# ESP32_ublox_IMU.net
KiCad netlist of a schematic drawn in Altium Designer
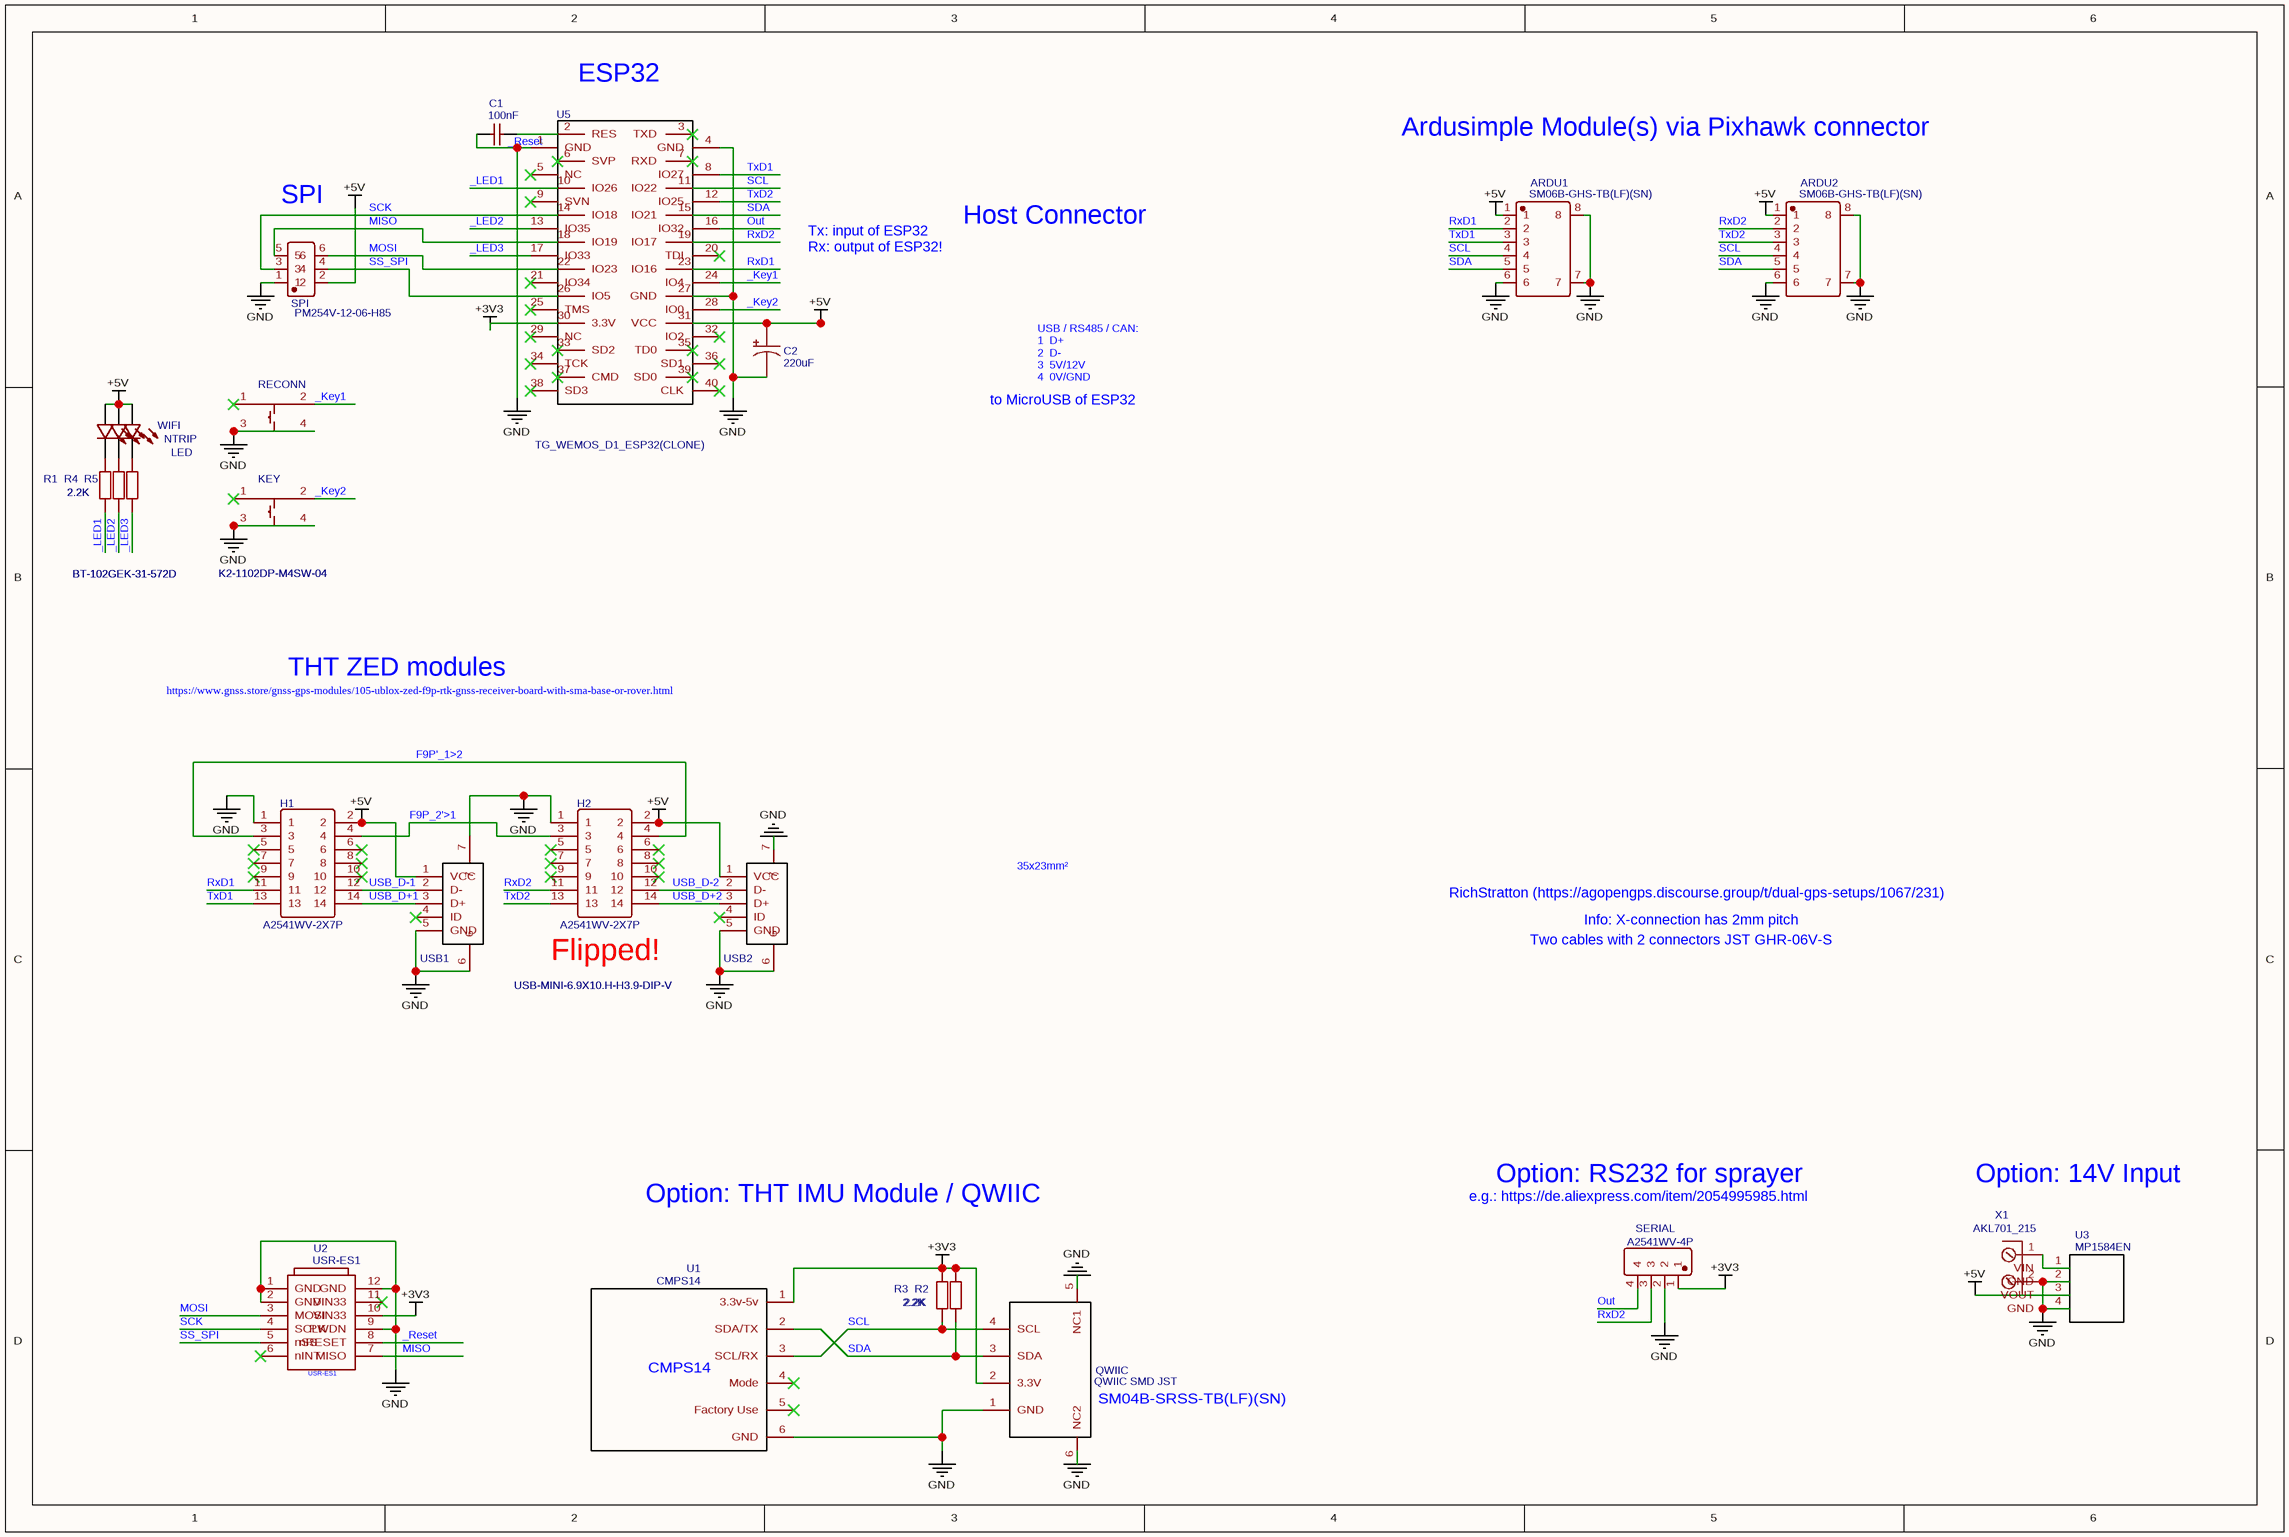
[diagram p0: ESP32 ublox IMU.schdoc]

(export (version "E")
  (design (tool "Eeschema 10.0.6"))
  (components
    (comp (ref "ARDU1")
      (value "SM06B-GHS-TB(LF)(SN)")
      (fields (field (name "BOM_SUPPLIER PART") "C133065") (field (name "CONTRIBUTOR") "LCSC"))
      (libsource (lib "altium-import") (part "root_0_SM06B-GHS-TB(LF)(SN)_"))
    )
    (comp (ref "ARDU2")
      (value "SM06B-GHS-TB(LF)(SN)")
      (fields (field (name "BOM_SUPPLIER PART") "C133065") (field (name "CONTRIBUTOR") "LCSC"))
      (libsource (lib "altium-import") (part "root_0_SM06B-GHS-TB(LF)(SN)_"))
    )
    (comp (ref "C1")
      (value "100nF")
      (fields
        (field (name "BOM_SUPPLIER PART") "C236029")
        (field (name "BOM_MANUFACTURER PART") "C320C104K5R5TA7303")
        (field (name "CONTRIBUTOR") "LCSC")
      )
      (libsource (lib "altium-import") (part "root_0_100nF_"))
    )
    (comp (ref "C2")
      (value "220uF")
      (fields
        (field (name "BOM_SUPPLIER PART") "C225866")
        (field (name "BOM_MANUFACTURER PART") "UPW1A221MED1TD")
        (field (name "CONTRIBUTOR") "LCSC")
      )
      (libsource (lib "altium-import") (part "root_0_220uF_"))
    )
    (comp (ref "H1")
      (value "A2541WV-2X7P")
      (fields
        (field (name "BOM_SUPPLIER PART") "C225522")
        (field (name "BOM_MANUFACTURER PART") "A2541WV-2x7P")
        (field (name "CONTRIBUTOR") "LCSC")
      )
      (libsource (lib "altium-import") (part "root_0_A2541WV-2X7P_"))
    )
    (comp (ref "H2")
      (value "A2541WV-2X7P")
      (fields
        (field (name "BOM_SUPPLIER PART") "C225522")
        (field (name "BOM_MANUFACTURER PART") "A2541WV-2x7P")
        (field (name "CONTRIBUTOR") "LCSC")
      )
      (libsource (lib "altium-import") (part "root_0_A2541WV-2X7P_"))
    )
    (comp (ref "KEY")
      (value "K2-1102DP-M4SW-04")
      (fields (field (name "BOM_SUPPLIER PART") "C136678") (field (name "CONTRIBUTOR") "LCSC"))
      (libsource (lib "altium-import") (part "root_0_K2-1102DP-M4SW-04_"))
    )
    (comp (ref "LED")
      (value "BT-102GEK-31-572D")
      (fields (field (name "BOM_SUPPLIER PART") "C93096"))
      (libsource (lib "altium-import") (part "root_3_BT-102GEK-31-572D_"))
    )
    (comp (ref "NTRIP")
      (value "BT-102GEK-31-572D")
      (fields (field (name "BOM_SUPPLIER PART") "C93096"))
      (libsource (lib "altium-import") (part "root_3_BT-102GEK-31-572D_"))
    )
    (comp (ref "QWIIC")
      (value "QWIIC SMD JST")
      (fields
        (field (name "BOM_MANUFACTURER PART") "SM04B-SRSS-TB(LF)(SN)")
        (field (name "BOM_SUPPLIER PART") "PRT-14417")
        (field (name "CONTRIBUTOR") "donhagen")
      )
      (libsource (lib "altium-import") (part "root_1_QWIIC SMD JST_"))
    )
    (comp (ref "R1")
      (value "2.2K")
      (fields
        (field (name "BOM_SUPPLIER PART") "C274429")
        (field (name "BOM_MANUFACTURER PART") "RNU18F2201A520NH")
        (field (name "CONTRIBUTOR") "LCSC")
      )
      (libsource (lib "altium-import") (part "root_1_2.2K_"))
    )
    (comp (ref "R2")
      (value "2.2K")
      (fields
        (field (name "BOM_SUPPLIER PART") "C274429")
        (field (name "BOM_MANUFACTURER PART") "RNU18F2201A520NH")
        (field (name "CONTRIBUTOR") "LCSC")
      )
      (libsource (lib "altium-import") (part "root_1_2.2K_"))
    )
    (comp (ref "R3")
      (value "2.2K")
      (fields
        (field (name "BOM_SUPPLIER PART") "C274429")
        (field (name "BOM_MANUFACTURER PART") "RNU18F2201A520NH")
        (field (name "CONTRIBUTOR") "LCSC")
      )
      (libsource (lib "altium-import") (part "root_1_2.2K_"))
    )
    (comp (ref "R4")
      (value "2.2K")
      (fields
        (field (name "BOM_SUPPLIER PART") "C274429")
        (field (name "BOM_MANUFACTURER PART") "RNU18F2201A520NH")
        (field (name "CONTRIBUTOR") "LCSC")
      )
      (libsource (lib "altium-import") (part "root_1_2.2K_"))
    )
    (comp (ref "R5")
      (value "2.2K")
      (fields
        (field (name "BOM_SUPPLIER PART") "C274429")
        (field (name "BOM_MANUFACTURER PART") "RNU18F2201A520NH")
        (field (name "CONTRIBUTOR") "LCSC")
      )
      (libsource (lib "altium-import") (part "root_1_2.2K_"))
    )
    (comp (ref "RECONN")
      (value "K2-1102DP-M4SW-04")
      (fields (field (name "BOM_SUPPLIER PART") "C136678") (field (name "CONTRIBUTOR") "LCSC"))
      (libsource (lib "altium-import") (part "root_0_K2-1102DP-M4SW-04_"))
    )
    (comp (ref "SERIAL")
      (value "A2541WV-4P")
      (fields (field (name "BOM_SUPPLIER PART") "C225479") (field (name "CONTRIBUTOR") "LCSC"))
      (libsource (lib "altium-import") (part "root_0_A2541WV-4P_"))
    )
    (comp (ref "SPI")
      (value "PM254V-12-06-H85")
      (fields (field (name "BOM_SUPPLIER PART") "C541853") (field (name "CONTRIBUTOR") "LCSC"))
      (libsource (lib "altium-import") (part "root_0_PM254V-12-06-H85_"))
    )
    (comp (ref "U1")
      (value "CMPS14")
      (fields (field (name "CONTRIBUTOR") "FixyNeko"))
      (libsource (lib "altium-import") (part "root_0_CMPS14_"))
    )
    (comp (ref "U2")
      (value "USR-ES1")
      (fields (field (name "CONTRIBUTOR") "tomaz.dezman_0109"))
      (libsource (lib "altium-import") (part "root_0_USR-ES1_"))
    )
    (comp (ref "U3")
      (value "MP1584EN")
      (fields (field (name "CONTRIBUTOR") "babeinlovexd"))
      (libsource (lib "altium-import") (part "root_0_MP1584EN_"))
    )
    (comp (ref "U5")
      (value "TG_WEMOS_D1_ESP32(CLONE)")
      (fields
        (field (name "BOM_MANUFACTURER PART") "New SchematicLib")
        (field (name "BOM_SUPPLIER PART") "undefined")
        (field (name "CONTRIBUTOR") "John Archbold")
      )
      (libsource (lib "altium-import") (part "root_0_TG_WEMOS_D1_ESP32(CLONE)_"))
    )
    (comp (ref "USB1")
      (value "USB-MINI-6.9X10.H-H3.9-DIP-V")
      (fields (field (name "BOM_SUPPLIER PART") "C13453") (field (name "CONTRIBUTOR") "LCSC"))
      (libsource (lib "altium-import") (part "root_3_USB-MINI-6.9X10.H-H3.9-DIP-V_"))
    )
    (comp (ref "USB2")
      (value "USB-MINI-6.9X10.H-H3.9-DIP-V")
      (fields (field (name "BOM_SUPPLIER PART") "C13453") (field (name "CONTRIBUTOR") "LCSC"))
      (libsource (lib "altium-import") (part "root_3_USB-MINI-6.9X10.H-H3.9-DIP-V_"))
    )
    (comp (ref "WIFI")
      (value "BT-102GEK-31-572D")
      (fields (field (name "BOM_SUPPLIER PART") "C93096"))
      (libsource (lib "altium-import") (part "root_3_BT-102GEK-31-572D_"))
    )
    (comp (ref "X1") (value "AKL701_215") (libsource (lib "altium-import") (part "root_0_AKL701_215_")))
  )
  (nets
    (net (code "1") (name "+3V3") (class "Default")
      (node (ref "QWIIC") (pin "2") (pinfunction "3.3V_2") (pintype "passive"))
      (node (ref "R2") (pin "2") (pinfunction "2_2") (pintype "passive"))
      (node (ref "R3") (pin "2") (pinfunction "2_2") (pintype "passive"))
      (node (ref "SERIAL") (pin "1") (pinfunction "1_1") (pintype "passive"))
      (node (ref "U1") (pin "1") (pinfunction "3.3v-5v_1") (pintype "passive"))
      (node (ref "U2") (pin "10") (pinfunction "VIN33_10") (pintype "passive"))
      (node (ref "U5") (pin "30") (pinfunction "3.3V_30") (pintype "passive"))
    )
    (net (code "2") (name "+5V") (class "Default")
      (node (ref "ARDU1") (pin "1") (pinfunction "1_1") (pintype "passive"))
      (node (ref "ARDU2") (pin "1") (pinfunction "1_1") (pintype "passive"))
      (node (ref "C2") (pin "1") (pinfunction "1_1") (pintype "passive"))
      (node (ref "H1") (pin "2") (pinfunction "2_2") (pintype "passive"))
      (node (ref "H2") (pin "2") (pinfunction "2_2") (pintype "passive"))
      (node (ref "LED") (pin "1") (pinfunction "1_1") (pintype "passive"))
      (node (ref "NTRIP") (pin "1") (pinfunction "1_1") (pintype "passive"))
      (node (ref "SPI") (pin "2") (pinfunction "2_2") (pintype "passive"))
      (node (ref "U3") (pin "3") (pinfunction "VOUT_3") (pintype "passive"))
      (node (ref "U5") (pin "31") (pinfunction "VCC_31") (pintype "passive"))
      (node (ref "USB1") (pin "1") (pinfunction "VCC_1") (pintype "passive"))
      (node (ref "USB2") (pin "1") (pinfunction "VCC_1") (pintype "passive"))
      (node (ref "WIFI") (pin "1") (pinfunction "1_1") (pintype "passive"))
    )
    (net (code "3") (name "/F9P'_1>2") (class "Default")
      (node (ref "H1") (pin "3") (pinfunction "3_3") (pintype "passive"))
      (node (ref "H2") (pin "4") (pinfunction "4_4") (pintype "passive"))
    )
    (net (code "4") (name "/F9P_2'>1") (class "Default")
      (node (ref "H1") (pin "4") (pinfunction "4_4") (pintype "passive"))
      (node (ref "H2") (pin "3") (pinfunction "3_3") (pintype "passive"))
    )
    (net (code "5") (name "/MISO") (class "Default")
      (node (ref "SPI") (pin "5") (pinfunction "5_5") (pintype "passive"))
      (node (ref "U2") (pin "7") (pinfunction "MISO_7") (pintype "passive"))
      (node (ref "U5") (pin "18") (pinfunction "IO19_18") (pintype "passive"))
    )
    (net (code "6") (name "/MOSI") (class "Default")
      (node (ref "SPI") (pin "6") (pinfunction "6_6") (pintype "passive"))
      (node (ref "U2") (pin "3") (pinfunction "MOSI_3") (pintype "passive"))
      (node (ref "U5") (pin "22") (pinfunction "IO23_22") (pintype "passive"))
    )
    (net (code "7") (name "/Out") (class "Default")
      (node (ref "SERIAL") (pin "4") (pinfunction "4_4") (pintype "passive"))
      (node (ref "U5") (pin "16") (pinfunction "IO32_16") (pintype "passive"))
    )
    (net (code "8") (name "/RxD1") (class "Default")
      (node (ref "ARDU1") (pin "2") (pinfunction "2_2") (pintype "passive"))
      (node (ref "H1") (pin "11") (pinfunction "11_11") (pintype "passive"))
      (node (ref "U5") (pin "23") (pinfunction "IO16_23") (pintype "passive"))
    )
    (net (code "9") (name "/RxD2") (class "Default")
      (node (ref "ARDU2") (pin "2") (pinfunction "2_2") (pintype "passive"))
      (node (ref "H2") (pin "11") (pinfunction "11_11") (pintype "passive"))
      (node (ref "SERIAL") (pin "3") (pinfunction "3_3") (pintype "passive"))
      (node (ref "U5") (pin "19") (pinfunction "IO17_19") (pintype "passive"))
    )
    (net (code "10") (name "/SCK") (class "Default")
      (node (ref "SPI") (pin "3") (pinfunction "3_3") (pintype "passive"))
      (node (ref "U2") (pin "4") (pinfunction "SCLK_4") (pintype "passive"))
      (node (ref "U5") (pin "14") (pinfunction "IO18_14") (pintype "passive"))
    )
    (net (code "11") (name "/SCL") (class "Default")
      (node (ref "ARDU1") (pin "4") (pinfunction "4_4") (pintype "passive"))
      (node (ref "ARDU2") (pin "4") (pinfunction "4_4") (pintype "passive"))
      (node (ref "QWIIC") (pin "4") (pinfunction "SCL_4") (pintype "passive"))
      (node (ref "R3") (pin "1") (pinfunction "1_1") (pintype "passive"))
      (node (ref "U1") (pin "3") (pinfunction "SCL/RX_3") (pintype "passive"))
      (node (ref "U5") (pin "11") (pinfunction "IO22_11") (pintype "passive"))
    )
    (net (code "12") (name "/SDA") (class "Default")
      (node (ref "ARDU1") (pin "5") (pinfunction "5_5") (pintype "passive"))
      (node (ref "ARDU2") (pin "5") (pinfunction "5_5") (pintype "passive"))
      (node (ref "QWIIC") (pin "3") (pinfunction "SDA_3") (pintype "passive"))
      (node (ref "R2") (pin "1") (pinfunction "1_1") (pintype "passive"))
      (node (ref "U1") (pin "2") (pinfunction "SDA/TX_2") (pintype "passive"))
      (node (ref "U5") (pin "15") (pinfunction "IO21_15") (pintype "passive"))
    )
    (net (code "13") (name "/SS_SPI") (class "Default")
      (node (ref "SPI") (pin "4") (pinfunction "4_4") (pintype "passive"))
      (node (ref "U2") (pin "5") (pinfunction "nSS_5") (pintype "passive"))
      (node (ref "U5") (pin "26") (pinfunction "IO5_26") (pintype "passive"))
    )
    (net (code "14") (name "/TxD1") (class "Default")
      (node (ref "ARDU1") (pin "3") (pinfunction "3_3") (pintype "passive"))
      (node (ref "H1") (pin "13") (pinfunction "13_13") (pintype "passive"))
      (node (ref "U5") (pin "8") (pinfunction "IO27_8") (pintype "passive"))
    )
    (net (code "15") (name "/TxD2") (class "Default")
      (node (ref "ARDU2") (pin "3") (pinfunction "3_3") (pintype "passive"))
      (node (ref "H2") (pin "13") (pinfunction "13_13") (pintype "passive"))
      (node (ref "U5") (pin "12") (pinfunction "IO25_12") (pintype "passive"))
    )
    (net (code "16") (name "/USB_D+1") (class "Default")
      (node (ref "H1") (pin "14") (pinfunction "14_14") (pintype "passive"))
      (node (ref "USB1") (pin "3") (pinfunction "D+_3") (pintype "passive"))
    )
    (net (code "17") (name "/USB_D+2") (class "Default")
      (node (ref "H2") (pin "14") (pinfunction "14_14") (pintype "passive"))
      (node (ref "USB2") (pin "3") (pinfunction "D+_3") (pintype "passive"))
    )
    (net (code "18") (name "/USB_D-1") (class "Default")
      (node (ref "H1") (pin "12") (pinfunction "12_12") (pintype "passive"))
      (node (ref "USB1") (pin "2") (pinfunction "D-_2") (pintype "passive"))
    )
    (net (code "19") (name "/USB_D-2") (class "Default")
      (node (ref "H2") (pin "12") (pinfunction "12_12") (pintype "passive"))
      (node (ref "USB2") (pin "2") (pinfunction "D-_2") (pintype "passive"))
    )
    (net (code "20") (name "/_Key1") (class "Default")
      (node (ref "RECONN") (pin "2") (pinfunction "2_2") (pintype "passive"))
      (node (ref "U5") (pin "24") (pinfunction "IO4_24") (pintype "passive"))
    )
    (net (code "21") (name "/_Key2") (class "Default")
      (node (ref "KEY") (pin "2") (pinfunction "2_2") (pintype "passive"))
      (node (ref "U5") (pin "28") (pinfunction "IO0_28") (pintype "passive"))
    )
    (net (code "22") (name "/_LED1") (class "Default")
      (node (ref "R1") (pin "1") (pinfunction "1_1") (pintype "passive"))
      (node (ref "U5") (pin "10") (pinfunction "IO26_10") (pintype "passive"))
    )
    (net (code "23") (name "/_LED2") (class "Default")
      (node (ref "R4") (pin "1") (pinfunction "1_1") (pintype "passive"))
      (node (ref "U5") (pin "13") (pinfunction "IO35_13") (pintype "passive"))
    )
    (net (code "24") (name "/_LED3") (class "Default")
      (node (ref "R5") (pin "1") (pinfunction "1_1") (pintype "passive"))
      (node (ref "U5") (pin "17") (pinfunction "IO33_17") (pintype "passive"))
    )
    (net (code "25") (name "/_Reset") (class "Default")
      (node (ref "C1") (pin "2") (pinfunction "2_2") (pintype "passive"))
      (node (ref "U2") (pin "8") (pinfunction "nRESET_8") (pintype "passive"))
      (node (ref "U5") (pin "2") (pinfunction "RES_2") (pintype "passive"))
    )
    (net (code "26") (name "GND") (class "Default")
      (node (ref "ARDU1") (pin "6") (pinfunction "6_6") (pintype "passive"))
      (node (ref "ARDU1") (pin "7") (pinfunction "7_7") (pintype "passive"))
      (node (ref "ARDU1") (pin "8") (pinfunction "8_8") (pintype "passive"))
      (node (ref "ARDU2") (pin "6") (pinfunction "6_6") (pintype "passive"))
      (node (ref "ARDU2") (pin "7") (pinfunction "7_7") (pintype "passive"))
      (node (ref "ARDU2") (pin "8") (pinfunction "8_8") (pintype "passive"))
      (node (ref "C1") (pin "1") (pinfunction "1_1") (pintype "passive"))
      (node (ref "C2") (pin "2") (pinfunction "2_2") (pintype "passive"))
      (node (ref "H1") (pin "1") (pinfunction "1_1") (pintype "passive"))
      (node (ref "H2") (pin "1") (pinfunction "1_1") (pintype "passive"))
      (node (ref "KEY") (pin "3") (pinfunction "3_3") (pintype "passive"))
      (node (ref "KEY") (pin "4") (pinfunction "4_4") (pintype "passive"))
      (node (ref "QWIIC") (pin "1") (pinfunction "GND_1") (pintype "passive"))
      (node (ref "QWIIC") (pin "5") (pinfunction "NC1_5") (pintype "passive"))
      (node (ref "QWIIC") (pin "6") (pinfunction "NC2_6") (pintype "passive"))
      (node (ref "RECONN") (pin "3") (pinfunction "3_3") (pintype "passive"))
      (node (ref "RECONN") (pin "4") (pinfunction "4_4") (pintype "passive"))
      (node (ref "SERIAL") (pin "2") (pinfunction "2_2") (pintype "passive"))
      (node (ref "SPI") (pin "1") (pinfunction "1_1") (pintype "passive"))
      (node (ref "U1") (pin "6") (pinfunction "GND_6") (pintype "passive"))
      (node (ref "U2") (pin "1") (pinfunction "GND_1") (pintype "passive"))
      (node (ref "U2") (pin "12") (pinfunction "GND_12") (pintype "passive"))
      (node (ref "U2") (pin "2") (pinfunction "GND_2") (pintype "passive"))
      (node (ref "U2") (pin "9") (pinfunction "PWDN_9") (pintype "passive"))
      (node (ref "U3") (pin "2") (pinfunction "GND_2") (pintype "passive"))
      (node (ref "U3") (pin "4") (pinfunction "GND_4") (pintype "passive"))
      (node (ref "U5") (pin "1") (pinfunction "GND_1") (pintype "passive"))
      (node (ref "U5") (pin "27") (pinfunction "GND_27") (pintype "passive"))
      (node (ref "U5") (pin "4") (pinfunction "GND_4") (pintype "passive"))
      (node (ref "USB1") (pin "5") (pinfunction "GND_5") (pintype "passive"))
      (node (ref "USB1") (pin "6") (pinfunction "6_6") (pintype "passive"))
      (node (ref "USB1") (pin "7") (pinfunction "7_7") (pintype "passive"))
      (node (ref "USB2") (pin "5") (pinfunction "GND_5") (pintype "passive"))
      (node (ref "USB2") (pin "6") (pinfunction "6_6") (pintype "passive"))
      (node (ref "USB2") (pin "7") (pinfunction "7_7") (pintype "passive"))
      (node (ref "X1") (pin "2") (pinfunction "2_2") (pintype "passive"))
    )
    (net (code "27") (name "Net-(LED-Pad2)") (class "Default")
      (node (ref "LED") (pin "2") (pinfunction "2_2") (pintype "passive"))
      (node (ref "R5") (pin "2") (pinfunction "2_2") (pintype "passive"))
    )
    (net (code "28") (name "Net-(NTRIP-Pad2)") (class "Default")
      (node (ref "NTRIP") (pin "2") (pinfunction "2_2") (pintype "passive"))
      (node (ref "R4") (pin "2") (pinfunction "2_2") (pintype "passive"))
    )
    (net (code "29") (name "Net-(R1-Pad2)") (class "Default")
      (node (ref "R1") (pin "2") (pinfunction "2_2") (pintype "passive"))
      (node (ref "WIFI") (pin "2") (pinfunction "2_2") (pintype "passive"))
    )
    (net (code "30") (name "Net-(U3-VIN)") (class "Default")
      (node (ref "U3") (pin "1") (pinfunction "VIN_1") (pintype "passive"))
      (node (ref "X1") (pin "1") (pinfunction "1_1") (pintype "passive"))
    )
    (net (code "31") (name "unconnected-(H1-Pad5)") (class "Default")
      (node (ref "H1") (pin "5") (pinfunction "5_5") (pintype "passive+no_connect"))
    )
    (net (code "32") (name "unconnected-(H1-Pad6)") (class "Default")
      (node (ref "H1") (pin "6") (pinfunction "6_6") (pintype "passive+no_connect"))
    )
    (net (code "33") (name "unconnected-(H1-Pad7)") (class "Default")
      (node (ref "H1") (pin "7") (pinfunction "7_7") (pintype "passive+no_connect"))
    )
    (net (code "34") (name "unconnected-(H1-Pad8)") (class "Default")
      (node (ref "H1") (pin "8") (pinfunction "8_8") (pintype "passive+no_connect"))
    )
    (net (code "35") (name "unconnected-(H1-Pad9)") (class "Default")
      (node (ref "H1") (pin "9") (pinfunction "9_9") (pintype "passive+no_connect"))
    )
    (net (code "36") (name "unconnected-(H1-Pad10)") (class "Default")
      (node (ref "H1") (pin "10") (pinfunction "10_10") (pintype "passive+no_connect"))
    )
    (net (code "37") (name "unconnected-(H2-Pad5)") (class "Default")
      (node (ref "H2") (pin "5") (pinfunction "5_5") (pintype "passive+no_connect"))
    )
    (net (code "38") (name "unconnected-(H2-Pad6)") (class "Default")
      (node (ref "H2") (pin "6") (pinfunction "6_6") (pintype "passive+no_connect"))
    )
    (net (code "39") (name "unconnected-(H2-Pad7)") (class "Default")
      (node (ref "H2") (pin "7") (pinfunction "7_7") (pintype "passive+no_connect"))
    )
    (net (code "40") (name "unconnected-(H2-Pad8)") (class "Default")
      (node (ref "H2") (pin "8") (pinfunction "8_8") (pintype "passive+no_connect"))
    )
    (net (code "41") (name "unconnected-(H2-Pad9)") (class "Default")
      (node (ref "H2") (pin "9") (pinfunction "9_9") (pintype "passive+no_connect"))
    )
    (net (code "42") (name "unconnected-(H2-Pad10)") (class "Default")
      (node (ref "H2") (pin "10") (pinfunction "10_10") (pintype "passive+no_connect"))
    )
    (net (code "43") (name "unconnected-(KEY-Pad1)") (class "Default")
      (node (ref "KEY") (pin "1") (pinfunction "1_1") (pintype "passive+no_connect"))
    )
    (net (code "44") (name "unconnected-(RECONN-Pad1)") (class "Default")
      (node (ref "RECONN") (pin "1") (pinfunction "1_1") (pintype "passive+no_connect"))
    )
    (net (code "45") (name "unconnected-(U1-Factory_Use-Pad5)") (class "Default")
      (node (ref "U1") (pin "5") (pinfunction "Factory_Use_5") (pintype "passive+no_connect"))
    )
    (net (code "46") (name "unconnected-(U1-Mode-Pad4)") (class "Default")
      (node (ref "U1") (pin "4") (pinfunction "Mode_4") (pintype "passive+no_connect"))
    )
    (net (code "47") (name "unconnected-(U2-VIN33-Pad11)") (class "Default")
      (node (ref "U2") (pin "11") (pinfunction "VIN33_11") (pintype "passive+no_connect"))
    )
    (net (code "48") (name "unconnected-(U2-nINT-Pad6)") (class "Default")
      (node (ref "U2") (pin "6") (pinfunction "nINT_6") (pintype "passive+no_connect"))
    )
    (net (code "49") (name "unconnected-(U5-CLK-Pad40)") (class "Default")
      (node (ref "U5") (pin "40") (pinfunction "CLK_40") (pintype "passive+no_connect"))
    )
    (net (code "50") (name "unconnected-(U5-CMD-Pad37)") (class "Default")
      (node (ref "U5") (pin "37") (pinfunction "CMD_37") (pintype "passive+no_connect"))
    )
    (net (code "51") (name "unconnected-(U5-IO2-Pad32)") (class "Default")
      (node (ref "U5") (pin "32") (pinfunction "IO2_32") (pintype "passive+no_connect"))
    )
    (net (code "52") (name "unconnected-(U5-IO34-Pad21)") (class "Default")
      (node (ref "U5") (pin "21") (pinfunction "IO34_21") (pintype "passive+no_connect"))
    )
    (net (code "53") (name "unconnected-(U5-NC-Pad5)") (class "Default")
      (node (ref "U5") (pin "5") (pinfunction "NC_5") (pintype "passive+no_connect"))
    )
    (net (code "54") (name "unconnected-(U5-NC-Pad29)") (class "Default")
      (node (ref "U5") (pin "29") (pinfunction "NC_29") (pintype "passive+no_connect"))
    )
    (net (code "55") (name "unconnected-(U5-RXD-Pad7)") (class "Default")
      (node (ref "U5") (pin "7") (pinfunction "RXD_7") (pintype "passive+no_connect"))
    )
    (net (code "56") (name "unconnected-(U5-SD0-Pad39)") (class "Default")
      (node (ref "U5") (pin "39") (pinfunction "SD0_39") (pintype "passive+no_connect"))
    )
    (net (code "57") (name "unconnected-(U5-SD1-Pad36)") (class "Default")
      (node (ref "U5") (pin "36") (pinfunction "SD1_36") (pintype "passive+no_connect"))
    )
    (net (code "58") (name "unconnected-(U5-SD2-Pad33)") (class "Default")
      (node (ref "U5") (pin "33") (pinfunction "SD2_33") (pintype "passive+no_connect"))
    )
    (net (code "59") (name "unconnected-(U5-SD3-Pad38)") (class "Default")
      (node (ref "U5") (pin "38") (pinfunction "SD3_38") (pintype "passive+no_connect"))
    )
    (net (code "60") (name "unconnected-(U5-SVN-Pad9)") (class "Default")
      (node (ref "U5") (pin "9") (pinfunction "SVN_9") (pintype "passive+no_connect"))
    )
    (net (code "61") (name "unconnected-(U5-SVP-Pad6)") (class "Default")
      (node (ref "U5") (pin "6") (pinfunction "SVP_6") (pintype "passive+no_connect"))
    )
    (net (code "62") (name "unconnected-(U5-TCK-Pad34)") (class "Default")
      (node (ref "U5") (pin "34") (pinfunction "TCK_34") (pintype "passive+no_connect"))
    )
    (net (code "63") (name "unconnected-(U5-TD0-Pad35)") (class "Default")
      (node (ref "U5") (pin "35") (pinfunction "TD0_35") (pintype "passive+no_connect"))
    )
    (net (code "64") (name "unconnected-(U5-TDI-Pad20)") (class "Default")
      (node (ref "U5") (pin "20") (pinfunction "TDI_20") (pintype "passive+no_connect"))
    )
    (net (code "65") (name "unconnected-(U5-TMS-Pad25)") (class "Default")
      (node (ref "U5") (pin "25") (pinfunction "TMS_25") (pintype "passive+no_connect"))
    )
    (net (code "66") (name "unconnected-(U5-TXD-Pad3)") (class "Default")
      (node (ref "U5") (pin "3") (pinfunction "TXD_3") (pintype "passive+no_connect"))
    )
    (net (code "67") (name "unconnected-(USB1-ID-Pad4)") (class "Default")
      (node (ref "USB1") (pin "4") (pinfunction "ID_4") (pintype "passive+no_connect"))
    )
    (net (code "68") (name "unconnected-(USB2-ID-Pad4)") (class "Default")
      (node (ref "USB2") (pin "4") (pinfunction "ID_4") (pintype "passive+no_connect"))
    )
  )
)
